# MCU.net
KiCad netlist of a schematic drawn in Altium Designer
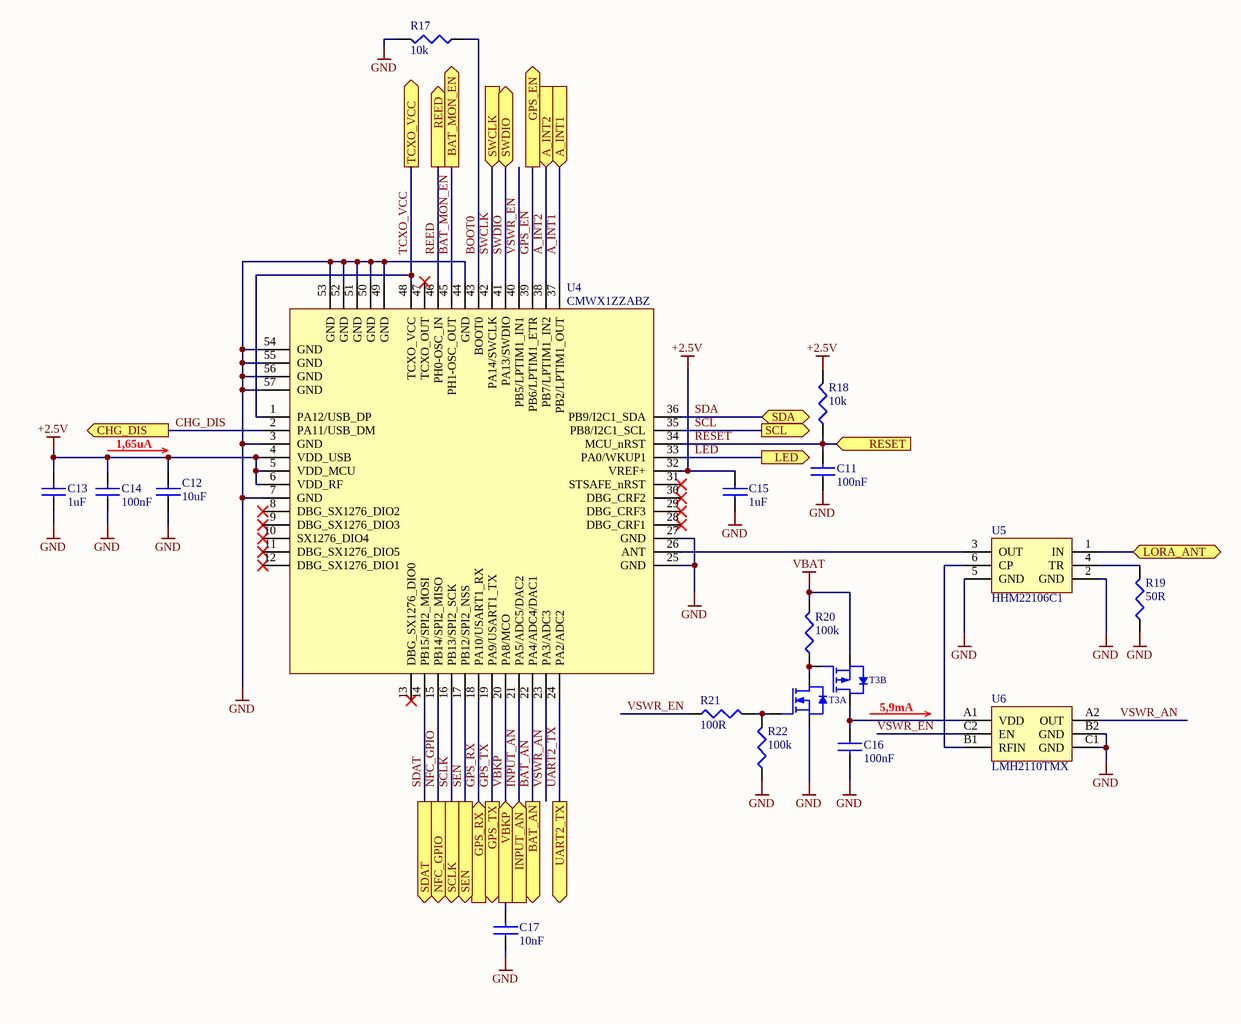
[diagram p0: MCU.SchDoc]

(export (version "E")
  (design (tool "Eeschema 10.0.6"))
  (components
    (comp (ref "C11")
      (value "100nF")
      (footprint "CAP0402")
      (fields
        (field (name "MANUFACTURER") "Multicomp")
        (field (name "MANUFACTURER PART NUMBER") "MC0402X104J160CT")
        (field (name "TOLERANCE") "5%")
      )
      (libsource (lib "Passive") (part "C - 100nF/0402"))
    )
    (comp (ref "C12")
      (value "10uF")
      (footprint "CAP0603")
      (description "10uf/0603/20%")
      (fields
        (field (name "MANUFACTURER") "KEMET")
        (field (name "MANUFACTURER PART NUMBER") "C0603C106M8PACTU")
      )
      (libsource (lib "pira-smart-schlib") (part "10uF"))
    )
    (comp (ref "C13")
      (value "1uF")
      (footprint "CAP0402")
      (description "CAP CER 1UF 10V 20% X5R 0402")
      (fields
        (field (name "MANUFACTURER") "Murata")
        (field (name "MANUFACTURER PART NUMBER") "GRM155R61A105ME15D")
      )
      (libsource (lib "Passive") (part "C - 1uF/0402"))
    )
    (comp (ref "C14")
      (value "100nF")
      (footprint "CAP0402")
      (fields
        (field (name "MANUFACTURER") "Multicomp")
        (field (name "MANUFACTURER PART NUMBER") "MC0402X104J160CT")
        (field (name "TOLERANCE") "5%")
      )
      (libsource (lib "Passive") (part "C - 100nF/0402"))
    )
    (comp (ref "C15")
      (value "1uF")
      (footprint "CAP0402")
      (description "CAP CER 1UF 10V 20% X5R 0402")
      (fields
        (field (name "MANUFACTURER") "Murata")
        (field (name "MANUFACTURER PART NUMBER") "GRM155R61A105ME15D")
      )
      (libsource (lib "Passive") (part "C - 1uF/0402"))
    )
    (comp (ref "C16")
      (value "100nF")
      (footprint "CAP0402")
      (fields
        (field (name "MANUFACTURER") "Multicomp")
        (field (name "MANUFACTURER PART NUMBER") "MC0402X104J160CT")
        (field (name "TOLERANCE") "5%")
      )
      (libsource (lib "Passive") (part "C - 100nF/0402"))
    )
    (comp (ref "C17")
      (value "10nF")
      (footprint "CAP0402")
      (description "CAP CER 10000PF 16V X7R 0402")
      (fields
        (field (name "MANUFACTURER") "Murata")
        (field (name "MANUFACTURER PART NUMBER") "GRM155R71C103KA01D")
      )
      (libsource (lib "Passive") (part "C - 10nF/0402"))
    )
    (comp (ref "R17")
      (value "10k")
      (footprint "RES0402")
      (fields
        (field (name "MANUFACTURER") "Multicomp")
        (field (name "MANUFACTURER PART NUMBER") "MCWR04X1002FTL")
        (field (name "TOLERANCE") "1%")
      )
      (libsource (lib "Passive") (part "R - 10k/0402"))
    )
    (comp (ref "R18")
      (value "10k")
      (footprint "RES0402")
      (fields
        (field (name "MANUFACTURER") "Multicomp")
        (field (name "MANUFACTURER PART NUMBER") "MCWR04X1002FTL")
        (field (name "TOLERANCE") "1%")
      )
      (libsource (lib "Passive") (part "R - 10k/0402"))
    )
    (comp (ref "R19")
      (value "50R")
      (footprint "RES0402")
      (description "SMD Chip Resistor, 0402 [1005 Metric], 50 ohm, FC Series, 30 V, Thin Film, 50 mW")
      (fields
        (field (name "MANUFACTURER") "Vishay")
        (field (name "MANUFACTURER PART NUMBER") "CRCW060351R0FKEA")
      )
      (libsource (lib "Passive") (part "R - 50R"))
    )
    (comp (ref "R20")
      (value "100k")
      (footprint "RES0402")
      (description "MULTICOMP   MCWR04X1003FTL   RES, THICK FILM, 100KOHM, 1%, 0.0625W")
      (fields
        (field (name "MANUFACTURER") "Multicomp")
        (field (name "MANUFACTURER PART NUMBER") "MCWR04X1003FTL")
      )
      (libsource (lib "Passive") (part "R - 100k/0402"))
    )
    (comp (ref "R21")
      (value "100R")
      (footprint "RES0402")
      (fields
        (field (name "MANUFACTURER") "Multicomp")
        (field (name "MANUFACTURER PART NUMBER") "MCMR04X1000FTL")
        (field (name "TOLERANCE") "1%")
      )
      (libsource (lib "Passive") (part "R - 100R/0402"))
    )
    (comp (ref "R22")
      (value "100k")
      (footprint "RES0402")
      (description "MULTICOMP   MCWR04X1003FTL   RES, THICK FILM, 100KOHM, 1%, 0.0625W")
      (fields
        (field (name "MANUFACTURER") "Multicomp")
        (field (name "MANUFACTURER PART NUMBER") "MCWR04X1003FTL")
      )
      (libsource (lib "Passive") (part "R - 100k/0402"))
    )
    (comp (ref "T3")
      (value "VT6M1T2CR")
      (footprint "VMT6")
      (description "Dual MOSFET, N and P Channel, 100 mA, 20 V, 2.5 ohm, 4.5 V, 1 V")
      (fields (field (name "AUTHOR") "Ciril Golob"))
      (libsource (lib "Active") (part "T_M - VT6M1T2CR"))
    )
    (comp (ref "U4")
      (value "CMWX1ZZABZ")
      (footprint "Lora Module ES0")
      (description "RF Module, FSK, OOK, LoRa, 4.8Kbps, 915MHz, -135.5dBm, 2.2V to 3.6V, I2C, SPI, UART, USB")
      (fields
        (field (name "MANUFACTURER") "Murata")
        (field (name "MANUFACTURER PART NUMBER") "CMWX1ZZABZ-091")
      )
      (libsource (lib "Active") (part "MCU - CMWX1ZZABZ"))
    )
    (comp (ref "U5")
      (value "HHM22106C1")
      (footprint "HHM22106C1")
      (description "Signal Conditioning DIRECTIONAL COUPLER 700-2700MHz")
      (fields (field (name "MANUFACTURER") "u-blox") (field (name "MANUFACTURER PART NUMBER") "MAX-M8Q-0"))
      (libsource (lib "Active") (part "RF - HHM22106C1"))
    )
    (comp (ref "U6")
      (value "LMH2110TMX")
      (footprint "DSBGA-6")
      (description "RF Detector IC GSM, EDGE, CDMA 50MHz ~ 8GHz -40dBm ~ 5dBm ±0,5dB")
      (fields (field (name "MANUFACTURER") "u-blox") (field (name "MANUFACTURER PART NUMBER") "MAX-M8Q-0"))
      (libsource (lib "Active") (part "RF - LMH2110TMX"))
    )
  )
  (nets
    (net (code "1") (name "+2.5V") (class "Default")
      (node (ref "C12") (pin "2") (pinfunction "2_2") (pintype "passive"))
      (node (ref "C13") (pin "2") (pinfunction "2_2") (pintype "passive"))
      (node (ref "C14") (pin "2") (pinfunction "2_2") (pintype "passive"))
      (node (ref "C15") (pin "2") (pinfunction "2_2") (pintype "passive"))
      (node (ref "R18") (pin "2") (pinfunction "2_2") (pintype "passive"))
      (node (ref "U4") (pin "32") (pinfunction "VREF+_32") (pintype "passive"))
      (node (ref "U4") (pin "4") (pinfunction "VDD_USB_4") (pintype "passive"))
      (node (ref "U4") (pin "5") (pinfunction "VDD_MCU_5") (pintype "passive"))
      (node (ref "U4") (pin "6") (pinfunction "VDD_RF_6") (pintype "passive"))
    )
    (net (code "2") (name "/A_INT1") (class "Default")
      (node (ref "U4") (pin "37") (pinfunction "PB2/LPTIM1_OUT_37") (pintype "passive"))
    )
    (net (code "3") (name "/A_INT2") (class "Default")
      (node (ref "U4") (pin "38") (pinfunction "PB7/LPTIM1_IN2_38") (pintype "passive"))
    )
    (net (code "4") (name "/BAT_AN") (class "Default")
      (node (ref "U4") (pin "22") (pinfunction "PA4/ADC4/DAC1_22") (pintype "passive"))
    )
    (net (code "5") (name "/BAT_MON_EN") (class "Default")
      (node (ref "U4") (pin "45") (pinfunction "PH1-OSC_OUT_45") (pintype "passive"))
    )
    (net (code "6") (name "/BOOT0") (class "Default")
      (node (ref "R17") (pin "1") (pinfunction "1_1") (pintype "passive"))
      (node (ref "U4") (pin "43") (pinfunction "BOOT0_43") (pintype "passive"))
    )
    (net (code "7") (name "/CHG_DIS") (class "Default")
      (node (ref "U4") (pin "2") (pinfunction "PA11/USB_DM_2") (pintype "passive"))
    )
    (net (code "8") (name "/GPS_EN") (class "Default")
      (node (ref "U4") (pin "39") (pinfunction "PB6/LPTIM1_ETR_39") (pintype "passive"))
    )
    (net (code "9") (name "/GPS_RX") (class "Default")
      (node (ref "U4") (pin "18") (pinfunction "PA10/USART1_RX_18") (pintype "passive"))
    )
    (net (code "10") (name "/GPS_TX") (class "Default")
      (node (ref "U4") (pin "19") (pinfunction "PA9/USART1_TX_19") (pintype "passive"))
    )
    (net (code "11") (name "/INPUT_AN") (class "Default")
      (node (ref "U4") (pin "21") (pinfunction "PA5/ADC5/DAC2_21") (pintype "passive"))
    )
    (net (code "12") (name "/LED") (class "Default")
      (node (ref "U4") (pin "33") (pinfunction "PA0/WKUP1_33") (pintype "passive"))
    )
    (net (code "13") (name "/LORA_ANT") (class "Default")
      (node (ref "U5") (pin "1") (pinfunction "IN_1") (pintype "passive"))
    )
    (net (code "14") (name "/NFC_GPIO") (class "Default")
      (node (ref "U4") (pin "15") (pinfunction "PB14/SPI2_MISO_15") (pintype "passive"))
    )
    (net (code "15") (name "/REED") (class "Default")
      (node (ref "U4") (pin "46") (pinfunction "PH0-OSC_IN_46") (pintype "passive"))
    )
    (net (code "16") (name "/RESET") (class "Default")
      (node (ref "C11") (pin "2") (pinfunction "2_2") (pintype "passive"))
      (node (ref "R18") (pin "1") (pinfunction "1_1") (pintype "passive"))
      (node (ref "U4") (pin "34") (pinfunction "MCU_nRST_34") (pintype "passive"))
    )
    (net (code "17") (name "/SCL") (class "Default")
      (node (ref "U4") (pin "35") (pinfunction "PB8/I2C1_SCL_35") (pintype "passive"))
    )
    (net (code "18") (name "/SCLK") (class "Default")
      (node (ref "U4") (pin "16") (pinfunction "PB13/SPI2_SCK_16") (pintype "passive"))
    )
    (net (code "19") (name "/SDA") (class "Default")
      (node (ref "U4") (pin "36") (pinfunction "PB9/I2C1_SDA_36") (pintype "passive"))
    )
    (net (code "20") (name "/SDAT") (class "Default")
      (node (ref "U4") (pin "14") (pinfunction "PB15/SPI2_MOSI_14") (pintype "passive"))
    )
    (net (code "21") (name "/SEN") (class "Default")
      (node (ref "U4") (pin "17") (pinfunction "PB12/SPI2_NSS_17") (pintype "passive"))
    )
    (net (code "22") (name "/SWCLK") (class "Default")
      (node (ref "U4") (pin "42") (pinfunction "PA14/SWCLK_42") (pintype "passive"))
    )
    (net (code "23") (name "/SWDIO") (class "Default")
      (node (ref "U4") (pin "41") (pinfunction "PA13/SWDIO_41") (pintype "passive"))
    )
    (net (code "24") (name "/TCXO_VCC") (class "Default")
      (node (ref "U4") (pin "1") (pinfunction "PA12/USB_DP_1") (pintype "passive"))
      (node (ref "U4") (pin "48") (pinfunction "TCXO_VCC_48") (pintype "passive"))
    )
    (net (code "25") (name "/UART2_TX") (class "Default")
      (node (ref "U4") (pin "24") (pinfunction "PA2/ADC2_24") (pintype "passive"))
    )
    (net (code "26") (name "/VBKP") (class "Default")
      (node (ref "C17") (pin "2") (pinfunction "2_2") (pintype "passive"))
      (node (ref "U4") (pin "20") (pinfunction "PA8/MCO_20") (pintype "passive"))
    )
    (net (code "27") (name "/VSWR_AN") (class "Default")
      (node (ref "U4") (pin "23") (pinfunction "PA3/ADC3_23") (pintype "passive"))
      (node (ref "U6") (pin "A2") (pinfunction "OUT_A2") (pintype "passive"))
    )
    (net (code "28") (name "/VSWR_EN") (class "Default")
      (node (ref "R21") (pin "1") (pinfunction "1_1") (pintype "passive"))
      (node (ref "U4") (pin "40") (pinfunction "PB5/LPTIM1_IN1_40") (pintype "passive"))
      (node (ref "U6") (pin "C2") (pinfunction "EN_C2") (pintype "passive"))
    )
    (net (code "29") (name "GND") (class "Default")
      (node (ref "C11") (pin "1") (pinfunction "1_1") (pintype "passive"))
      (node (ref "C12") (pin "1") (pinfunction "1_1") (pintype "passive"))
      (node (ref "C13") (pin "1") (pinfunction "1_1") (pintype "passive"))
      (node (ref "C14") (pin "1") (pinfunction "1_1") (pintype "passive"))
      (node (ref "C15") (pin "1") (pinfunction "1_1") (pintype "passive"))
      (node (ref "C16") (pin "2") (pinfunction "2_2") (pintype "passive"))
      (node (ref "C17") (pin "1") (pinfunction "1_1") (pintype "passive"))
      (node (ref "R17") (pin "2") (pinfunction "2_2") (pintype "passive"))
      (node (ref "R19") (pin "1") (pinfunction "1_1") (pintype "passive"))
      (node (ref "R22") (pin "1") (pinfunction "1_1") (pintype "passive"))
      (node (ref "T3") (pin "1") (pinfunction "S1_1") (pintype "passive"))
      (node (ref "U4") (pin "25") (pinfunction "GND_25") (pintype "passive"))
      (node (ref "U4") (pin "27") (pinfunction "GND_27") (pintype "passive"))
      (node (ref "U4") (pin "3") (pinfunction "GND_3") (pintype "passive"))
      (node (ref "U4") (pin "44") (pinfunction "GND_44") (pintype "passive"))
      (node (ref "U4") (pin "49") (pinfunction "GND_49") (pintype "passive"))
      (node (ref "U4") (pin "50") (pinfunction "GND_50") (pintype "passive"))
      (node (ref "U4") (pin "51") (pinfunction "GND_51") (pintype "passive"))
      (node (ref "U4") (pin "52") (pinfunction "GND_52") (pintype "passive"))
      (node (ref "U4") (pin "53") (pinfunction "GND_53") (pintype "passive"))
      (node (ref "U4") (pin "54") (pinfunction "GND_54") (pintype "passive"))
      (node (ref "U4") (pin "55") (pinfunction "GND_55") (pintype "passive"))
      (node (ref "U4") (pin "56") (pinfunction "GND_56") (pintype "passive"))
      (node (ref "U4") (pin "57") (pinfunction "GND_57") (pintype "passive"))
      (node (ref "U4") (pin "7") (pinfunction "GND_7") (pintype "passive"))
      (node (ref "U5") (pin "2") (pinfunction "GND_2") (pintype "passive"))
      (node (ref "U5") (pin "5") (pinfunction "GND_5") (pintype "passive"))
      (node (ref "U6") (pin "B2") (pinfunction "GND_B2") (pintype "passive"))
      (node (ref "U6") (pin "C1") (pinfunction "GND_C1") (pintype "passive"))
    )
    (net (code "30") (name "Net-(T3A-D1)") (class "Default")
      (node (ref "R20") (pin "1") (pinfunction "1_1") (pintype "passive"))
      (node (ref "T3") (pin "5") (pinfunction "G2_5") (pintype "passive"))
      (node (ref "T3") (pin "6") (pinfunction "D1_6") (pintype "passive"))
    )
    (net (code "31") (name "Net-(T3A-G1)") (class "Default")
      (node (ref "R21") (pin "2") (pinfunction "2_2") (pintype "passive"))
      (node (ref "R22") (pin "2") (pinfunction "2_2") (pintype "passive"))
      (node (ref "T3") (pin "2") (pinfunction "G1_2") (pintype "passive"))
    )
    (net (code "32") (name "Net-(T3B-D2)") (class "Default")
      (node (ref "C16") (pin "1") (pinfunction "1_1") (pintype "passive"))
      (node (ref "T3") (pin "3") (pinfunction "D2_3") (pintype "passive"))
      (node (ref "U6") (pin "A1") (pinfunction "VDD_A1") (pintype "passive"))
    )
    (net (code "33") (name "Net-(U4-ANT)") (class "Default")
      (node (ref "U4") (pin "26") (pinfunction "ANT_26") (pintype "passive"))
      (node (ref "U5") (pin "3") (pinfunction "OUT_3") (pintype "passive"))
    )
    (net (code "34") (name "Net-(U5-CP)") (class "Default")
      (node (ref "U5") (pin "6") (pinfunction "CP_6") (pintype "passive"))
      (node (ref "U6") (pin "B1") (pinfunction "RFIN_B1") (pintype "passive"))
    )
    (net (code "35") (name "Net-(U5-TR)") (class "Default")
      (node (ref "R19") (pin "2") (pinfunction "2_2") (pintype "passive"))
      (node (ref "U5") (pin "4") (pinfunction "TR_4") (pintype "passive"))
    )
    (net (code "36") (name "VBAT") (class "Default")
      (node (ref "R20") (pin "2") (pinfunction "2_2") (pintype "passive"))
      (node (ref "T3") (pin "4") (pinfunction "S2_4") (pintype "passive"))
    )
    (net (code "37") (name "unconnected-(U4-DBG_CRF1-Pad28)") (class "Default")
      (node (ref "U4") (pin "28") (pinfunction "DBG_CRF1_28") (pintype "passive+no_connect"))
    )
    (net (code "38") (name "unconnected-(U4-DBG_CRF2-Pad30)") (class "Default")
      (node (ref "U4") (pin "30") (pinfunction "DBG_CRF2_30") (pintype "passive+no_connect"))
    )
    (net (code "39") (name "unconnected-(U4-DBG_CRF3-Pad29)") (class "Default")
      (node (ref "U4") (pin "29") (pinfunction "DBG_CRF3_29") (pintype "passive+no_connect"))
    )
    (net (code "40") (name "unconnected-(U4-DBG_SX1276_DIO0-Pad13)") (class "Default")
      (node (ref "U4") (pin "13") (pinfunction "DBG_SX1276_DIO0_13") (pintype "passive+no_connect"))
    )
    (net (code "41") (name "unconnected-(U4-DBG_SX1276_DIO1-Pad12)") (class "Default")
      (node (ref "U4") (pin "12") (pinfunction "DBG_SX1276_DIO1_12") (pintype "passive+no_connect"))
    )
    (net (code "42") (name "unconnected-(U4-DBG_SX1276_DIO2-Pad8)") (class "Default")
      (node (ref "U4") (pin "8") (pinfunction "DBG_SX1276_DIO2_8") (pintype "passive+no_connect"))
    )
    (net (code "43") (name "unconnected-(U4-DBG_SX1276_DIO3-Pad9)") (class "Default")
      (node (ref "U4") (pin "9") (pinfunction "DBG_SX1276_DIO3_9") (pintype "passive+no_connect"))
    )
    (net (code "44") (name "unconnected-(U4-DBG_SX1276_DIO5-Pad11)") (class "Default")
      (node (ref "U4") (pin "11") (pinfunction "DBG_SX1276_DIO5_11") (pintype "passive+no_connect"))
    )
    (net (code "45") (name "unconnected-(U4-STSAFE_nRST-Pad31)") (class "Default")
      (node (ref "U4") (pin "31") (pinfunction "STSAFE_nRST_31") (pintype "passive+no_connect"))
    )
    (net (code "46") (name "unconnected-(U4-SX1276_DIO4-Pad10)") (class "Default")
      (node (ref "U4") (pin "10") (pinfunction "SX1276_DIO4_10") (pintype "passive+no_connect"))
    )
    (net (code "47") (name "unconnected-(U4-TCXO_OUT-Pad47)") (class "Default")
      (node (ref "U4") (pin "47") (pinfunction "TCXO_OUT_47") (pintype "passive+no_connect"))
    )
  )
)
